# Sheet1.net
KiCad netlist of a schematic drawn in Altium Designer
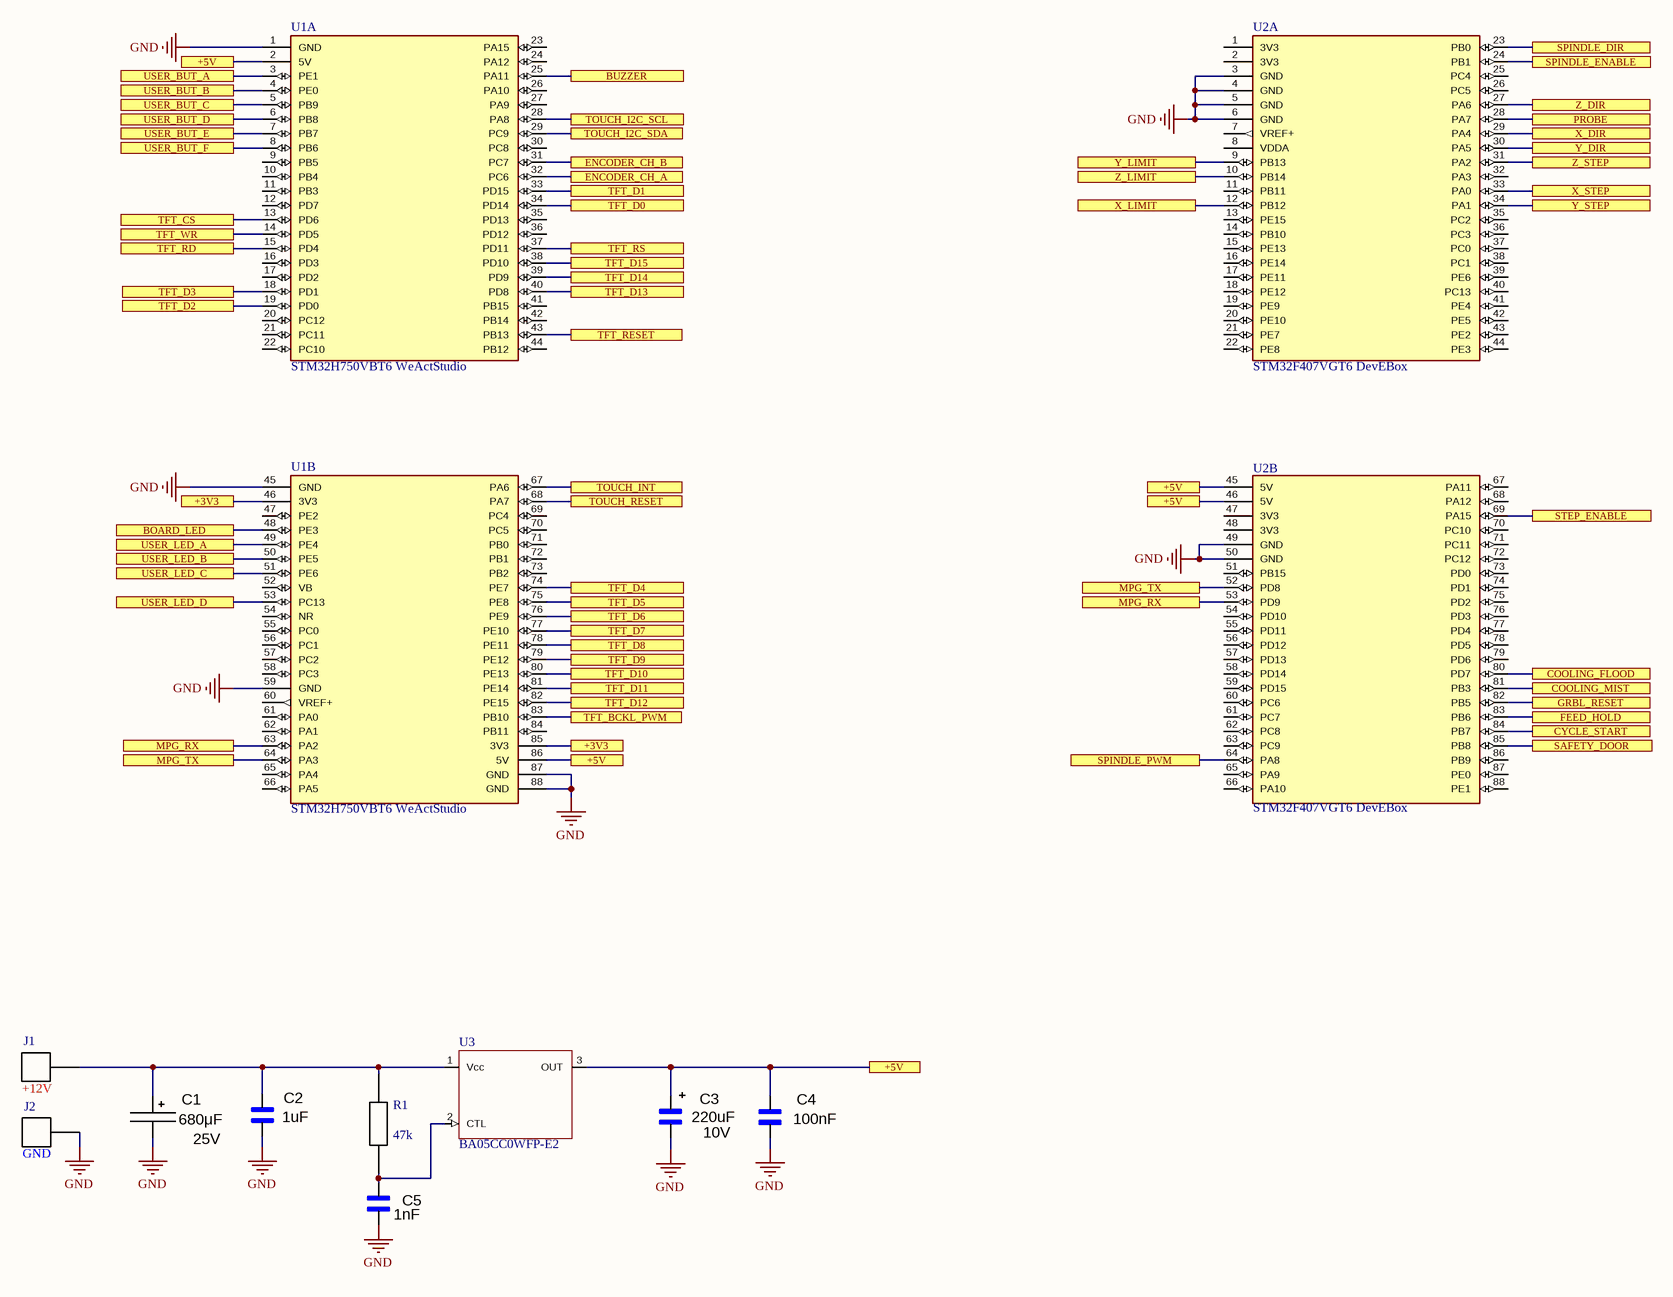
[diagram p0: Sheet1.SchDoc]

(export (version "E")
  (design (tool "Eeschema 10.0.6"))
  (components
    (comp (ref "C1")
      (value "680μF")
      (footprint "CAP 10x16")
      (fields
        (field (name "MANUFACTURER") "FUJICON")
        (field (name "VOLTAGE") "25V")
        (field (name "Comment") "680μF / 25V")
      )
      (libsource (lib "CAN_Library") (part "CAP Aluminium"))
    )
    (comp (ref "C2")
      (value "1uF")
      (footprint "*CAPC3326X230N")
      (description "C1210 10uF 35V X7R")
      (fields (field (name "MANUFACTURER") "SAMSUNG ELECTRO-MECHANICS"))
      (libsource (lib "CAN_Library") (part "CL32B106KLJNNNE"))
    )
    (comp (ref "C3")
      (value "220uF")
      (footprint "SMD 7343-43")
      (description "Cap Tant Solid 220uF 10V E CASE 10% _7.3 X 4.3 X 4mm_ SMD 7343-43 0.1 Ohm 125В°C T/R")
      (fields
        (field (name "MANUFACTURER") "VISHAY")
        (field (name "VOLTAGE") "10V")
        (field (name "Comment") "220uF 10V")
      )
      (libsource (lib "CAN_Library") (part "Cap Tant 220uF 10V Case E"))
    )
    (comp (ref "C4")
      (value "100nF")
      (footprint "SMD 0603")
      (description "C1210 10uF 35V X7R")
      (fields (field (name "MANUFACTURER") "SAMSUNG ELECTRO-MECHANICS"))
      (libsource (lib "CAN_Library") (part "CL32B106KLJNNNE"))
    )
    (comp (ref "C5")
      (value "1nF")
      (footprint "SMD 0603")
      (description "C1210 10uF 35V X7R")
      (fields (field (name "MANUFACTURER") "SAMSUNG ELECTRO-MECHANICS"))
      (libsource (lib "CAN_Library") (part "CL32B106KLJNNNE"))
    )
    (comp (ref "J1")
      (value "+12V")
      (footprint "Wire")
      (description "Wire")
      (libsource (lib "CAN_Library") (part "Wire"))
    )
    (comp (ref "J2")
      (value "GND")
      (footprint "Wire")
      (description "Wire")
      (libsource (lib "CAN_Library") (part "Wire"))
    )
    (comp (ref "R1")
      (value "47k")
      (footprint "SMD 0805")
      (description "RES")
      (libsource (lib "CAN_Library") (part "Resistor_1"))
    )
    (comp (ref "U1")
      (value "STM32H750VBT6 WeActStudio")
      (footprint "WeActStudio STM32H750VBT6")
      (libsource (lib "CAN_Library") (part "STM32H750VBT6 WeActStudio"))
    )
    (comp (ref "U2")
      (value "STM32F407VGT6 DevEBox")
      (footprint "DevEBox V3.0 STM32F407VGT6")
      (libsource (lib "CAN_Library") (part "STM32F407VGT6 DevEBox"))
    )
    (comp (ref "U3")
      (value "BA05CC0WFP-E2")
      (footprint "DPAK228P968X238-4N")
      (description "LDO Regulator")
      (fields (field (name "MANUFACTURER") "ROHM Semiconductor"))
      (libsource (lib "CAN_Library") (part "BA05CC0FP-E2"))
    )
  )
  (nets
    (net (code "1") (name "/+3V3") (class "Default")
      (node (ref "U1") (pin "46") (pinfunction "3V3_46") (pintype "power_in"))
      (node (ref "U1") (pin "85") (pinfunction "3V3_85") (pintype "power_in"))
    )
    (net (code "2") (name "/+5V") (class "Default")
      (node (ref "C3") (pin "1") (pinfunction "1_1") (pintype "passive"))
      (node (ref "C4") (pin "2") (pinfunction "2_2") (pintype "passive"))
      (node (ref "U1") (pin "2") (pinfunction "5V_2") (pintype "power_in"))
      (node (ref "U1") (pin "86") (pinfunction "5V_86") (pintype "power_in"))
      (node (ref "U2") (pin "45") (pinfunction "5V_45") (pintype "power_in"))
      (node (ref "U2") (pin "46") (pinfunction "5V_46") (pintype "power_in"))
      (node (ref "U3") (pin "3") (pinfunction "OUT_3") (pintype "passive"))
    )
    (net (code "3") (name "/BOARD_LED") (class "Default")
      (node (ref "U1") (pin "48") (pinfunction "PE3_48") (pintype "bidirectional"))
    )
    (net (code "4") (name "/BUZZER") (class "Default")
      (node (ref "U1") (pin "25") (pinfunction "PA11_25") (pintype "bidirectional"))
    )
    (net (code "5") (name "/COOLING_FLOOD") (class "Default")
      (node (ref "U2") (pin "80") (pinfunction "PD7_80") (pintype "bidirectional"))
    )
    (net (code "6") (name "/COOLING_MIST") (class "Default")
      (node (ref "U2") (pin "81") (pinfunction "PB3_81") (pintype "bidirectional"))
    )
    (net (code "7") (name "/CYCLE_START") (class "Default")
      (node (ref "U2") (pin "84") (pinfunction "PB7_84") (pintype "bidirectional"))
    )
    (net (code "8") (name "/ENCODER_CH_A") (class "Default")
      (node (ref "U1") (pin "32") (pinfunction "PC6_32") (pintype "bidirectional"))
    )
    (net (code "9") (name "/ENCODER_CH_B") (class "Default")
      (node (ref "U1") (pin "31") (pinfunction "PC7_31") (pintype "bidirectional"))
    )
    (net (code "10") (name "/FEED_HOLD") (class "Default")
      (node (ref "U2") (pin "83") (pinfunction "PB6_83") (pintype "bidirectional"))
    )
    (net (code "11") (name "/GRBL_RESET") (class "Default")
      (node (ref "U2") (pin "82") (pinfunction "PB5_82") (pintype "bidirectional"))
    )
    (net (code "12") (name "/MPG_RX") (class "Default")
      (node (ref "U1") (pin "63") (pinfunction "PA2_63") (pintype "bidirectional"))
      (node (ref "U2") (pin "53") (pinfunction "PD9_53") (pintype "bidirectional"))
    )
    (net (code "13") (name "/MPG_TX") (class "Default")
      (node (ref "U1") (pin "64") (pinfunction "PA3_64") (pintype "bidirectional"))
      (node (ref "U2") (pin "52") (pinfunction "PD8_52") (pintype "bidirectional"))
    )
    (net (code "14") (name "/PROBE") (class "Default")
      (node (ref "U2") (pin "28") (pinfunction "PA7_28") (pintype "bidirectional"))
    )
    (net (code "15") (name "/SAFETY_DOOR") (class "Default")
      (node (ref "U2") (pin "85") (pinfunction "PB8_85") (pintype "bidirectional"))
    )
    (net (code "16") (name "/SPINDLE_DIR") (class "Default")
      (node (ref "U2") (pin "23") (pinfunction "PB0_23") (pintype "bidirectional"))
    )
    (net (code "17") (name "/SPINDLE_ENABLE") (class "Default")
      (node (ref "U2") (pin "24") (pinfunction "PB1_24") (pintype "bidirectional"))
    )
    (net (code "18") (name "/SPINDLE_PWM") (class "Default")
      (node (ref "U2") (pin "64") (pinfunction "PA8_64") (pintype "bidirectional"))
    )
    (net (code "19") (name "/STEP_ENABLE") (class "Default")
      (node (ref "U2") (pin "69") (pinfunction "PA15_69") (pintype "bidirectional"))
    )
    (net (code "20") (name "/TFT_BCKL_PWM") (class "Default")
      (node (ref "U1") (pin "83") (pinfunction "PB10_83") (pintype "bidirectional"))
    )
    (net (code "21") (name "/TFT_CS") (class "Default")
      (node (ref "U1") (pin "13") (pinfunction "PD6_13") (pintype "bidirectional"))
    )
    (net (code "22") (name "/TFT_D0") (class "Default")
      (node (ref "U1") (pin "34") (pinfunction "PD14_34") (pintype "bidirectional"))
    )
    (net (code "23") (name "/TFT_D1") (class "Default")
      (node (ref "U1") (pin "33") (pinfunction "PD15_33") (pintype "bidirectional"))
    )
    (net (code "24") (name "/TFT_D2") (class "Default")
      (node (ref "U1") (pin "19") (pinfunction "PD0_19") (pintype "bidirectional"))
    )
    (net (code "25") (name "/TFT_D3") (class "Default")
      (node (ref "U1") (pin "18") (pinfunction "PD1_18") (pintype "bidirectional"))
    )
    (net (code "26") (name "/TFT_D4") (class "Default")
      (node (ref "U1") (pin "74") (pinfunction "PE7_74") (pintype "bidirectional"))
    )
    (net (code "27") (name "/TFT_D5") (class "Default")
      (node (ref "U1") (pin "75") (pinfunction "PE8_75") (pintype "bidirectional"))
    )
    (net (code "28") (name "/TFT_D6") (class "Default")
      (node (ref "U1") (pin "76") (pinfunction "PE9_76") (pintype "bidirectional"))
    )
    (net (code "29") (name "/TFT_D7") (class "Default")
      (node (ref "U1") (pin "77") (pinfunction "PE10_77") (pintype "bidirectional"))
    )
    (net (code "30") (name "/TFT_D8") (class "Default")
      (node (ref "U1") (pin "78") (pinfunction "PE11_78") (pintype "bidirectional"))
    )
    (net (code "31") (name "/TFT_D9") (class "Default")
      (node (ref "U1") (pin "79") (pinfunction "PE12_79") (pintype "bidirectional"))
    )
    (net (code "32") (name "/TFT_D10") (class "Default")
      (node (ref "U1") (pin "80") (pinfunction "PE13_80") (pintype "bidirectional"))
    )
    (net (code "33") (name "/TFT_D11") (class "Default")
      (node (ref "U1") (pin "81") (pinfunction "PE14_81") (pintype "bidirectional"))
    )
    (net (code "34") (name "/TFT_D12") (class "Default")
      (node (ref "U1") (pin "82") (pinfunction "PE15_82") (pintype "bidirectional"))
    )
    (net (code "35") (name "/TFT_D13") (class "Default")
      (node (ref "U1") (pin "40") (pinfunction "PD8_40") (pintype "bidirectional"))
    )
    (net (code "36") (name "/TFT_D14") (class "Default")
      (node (ref "U1") (pin "39") (pinfunction "PD9_39") (pintype "bidirectional"))
    )
    (net (code "37") (name "/TFT_D15") (class "Default")
      (node (ref "U1") (pin "38") (pinfunction "PD10_38") (pintype "bidirectional"))
    )
    (net (code "38") (name "/TFT_RD") (class "Default")
      (node (ref "U1") (pin "15") (pinfunction "PD4_15") (pintype "bidirectional"))
    )
    (net (code "39") (name "/TFT_RESET") (class "Default")
      (node (ref "U1") (pin "43") (pinfunction "PB13_43") (pintype "bidirectional"))
    )
    (net (code "40") (name "/TFT_RS") (class "Default")
      (node (ref "U1") (pin "37") (pinfunction "PD11_37") (pintype "bidirectional"))
    )
    (net (code "41") (name "/TFT_WR") (class "Default")
      (node (ref "U1") (pin "14") (pinfunction "PD5_14") (pintype "bidirectional"))
    )
    (net (code "42") (name "/TOUCH_I2C_SCL") (class "Default")
      (node (ref "U1") (pin "28") (pinfunction "PA8_28") (pintype "bidirectional"))
    )
    (net (code "43") (name "/TOUCH_I2C_SDA") (class "Default")
      (node (ref "U1") (pin "29") (pinfunction "PC9_29") (pintype "bidirectional"))
    )
    (net (code "44") (name "/TOUCH_INT") (class "Default")
      (node (ref "U1") (pin "67") (pinfunction "PA6_67") (pintype "bidirectional"))
    )
    (net (code "45") (name "/TOUCH_RESET") (class "Default")
      (node (ref "U1") (pin "68") (pinfunction "PA7_68") (pintype "bidirectional"))
    )
    (net (code "46") (name "/USER_BUT_A") (class "Default")
      (node (ref "U1") (pin "3") (pinfunction "PE1_3") (pintype "bidirectional"))
    )
    (net (code "47") (name "/USER_BUT_B") (class "Default")
      (node (ref "U1") (pin "4") (pinfunction "PE0_4") (pintype "bidirectional"))
    )
    (net (code "48") (name "/USER_BUT_C") (class "Default")
      (node (ref "U1") (pin "5") (pinfunction "PB9_5") (pintype "bidirectional"))
    )
    (net (code "49") (name "/USER_BUT_D") (class "Default")
      (node (ref "U1") (pin "6") (pinfunction "PB8_6") (pintype "bidirectional"))
    )
    (net (code "50") (name "/USER_BUT_E") (class "Default")
      (node (ref "U1") (pin "7") (pinfunction "PB7_7") (pintype "bidirectional"))
    )
    (net (code "51") (name "/USER_BUT_F") (class "Default")
      (node (ref "U1") (pin "8") (pinfunction "PB6_8") (pintype "bidirectional"))
    )
    (net (code "52") (name "/USER_LED_A") (class "Default")
      (node (ref "U1") (pin "49") (pinfunction "PE4_49") (pintype "bidirectional"))
    )
    (net (code "53") (name "/USER_LED_B") (class "Default")
      (node (ref "U1") (pin "50") (pinfunction "PE5_50") (pintype "bidirectional"))
    )
    (net (code "54") (name "/USER_LED_C") (class "Default")
      (node (ref "U1") (pin "51") (pinfunction "PE6_51") (pintype "bidirectional"))
    )
    (net (code "55") (name "/USER_LED_D") (class "Default")
      (node (ref "U1") (pin "53") (pinfunction "PC13_53") (pintype "bidirectional"))
    )
    (net (code "56") (name "/X_DIR") (class "Default")
      (node (ref "U2") (pin "29") (pinfunction "PA4_29") (pintype "bidirectional"))
    )
    (net (code "57") (name "/X_LIMIT") (class "Default")
      (node (ref "U2") (pin "12") (pinfunction "PB12_12") (pintype "bidirectional"))
    )
    (net (code "58") (name "/X_STEP") (class "Default")
      (node (ref "U2") (pin "33") (pinfunction "PA0_33") (pintype "bidirectional"))
    )
    (net (code "59") (name "/Y_DIR") (class "Default")
      (node (ref "U2") (pin "30") (pinfunction "PA5_30") (pintype "bidirectional"))
    )
    (net (code "60") (name "/Y_LIMIT") (class "Default")
      (node (ref "U2") (pin "9") (pinfunction "PB13_9") (pintype "bidirectional"))
    )
    (net (code "61") (name "/Y_STEP") (class "Default")
      (node (ref "U2") (pin "34") (pinfunction "PA1_34") (pintype "bidirectional"))
    )
    (net (code "62") (name "/Z_DIR") (class "Default")
      (node (ref "U2") (pin "27") (pinfunction "PA6_27") (pintype "bidirectional"))
    )
    (net (code "63") (name "/Z_LIMIT") (class "Default")
      (node (ref "U2") (pin "10") (pinfunction "PB14_10") (pintype "bidirectional"))
    )
    (net (code "64") (name "/Z_STEP") (class "Default")
      (node (ref "U2") (pin "31") (pinfunction "PA2_31") (pintype "bidirectional"))
    )
    (net (code "65") (name "GND") (class "Default")
      (node (ref "C1") (pin "2") (pinfunction "2_2") (pintype "power_in"))
      (node (ref "C2") (pin "1") (pinfunction "1_1") (pintype "passive"))
      (node (ref "C3") (pin "2") (pinfunction "2_2") (pintype "passive"))
      (node (ref "C4") (pin "1") (pinfunction "1_1") (pintype "passive"))
      (node (ref "C5") (pin "1") (pinfunction "1_1") (pintype "passive"))
      (node (ref "J2") (pin "1") (pinfunction "1_1") (pintype "passive"))
      (node (ref "U1") (pin "1") (pinfunction "GND_1") (pintype "power_in"))
      (node (ref "U1") (pin "45") (pinfunction "GND_45") (pintype "power_in"))
      (node (ref "U1") (pin "59") (pinfunction "GND_59") (pintype "power_in"))
      (node (ref "U1") (pin "87") (pinfunction "GND_87") (pintype "power_in"))
      (node (ref "U1") (pin "88") (pinfunction "GND_88") (pintype "power_in"))
      (node (ref "U2") (pin "3") (pinfunction "GND_3") (pintype "power_in"))
      (node (ref "U2") (pin "4") (pinfunction "GND_4") (pintype "power_in"))
      (node (ref "U2") (pin "49") (pinfunction "GND_49") (pintype "power_in"))
      (node (ref "U2") (pin "5") (pinfunction "GND_5") (pintype "power_in"))
      (node (ref "U2") (pin "50") (pinfunction "GND_50") (pintype "power_in"))
      (node (ref "U2") (pin "6") (pinfunction "GND_6") (pintype "power_in"))
    )
    (net (code "66") (name "Net-(U3-CTL)") (class "Default")
      (node (ref "C5") (pin "2") (pinfunction "2_2") (pintype "passive"))
      (node (ref "R1") (pin "2") (pinfunction "2_2") (pintype "passive"))
      (node (ref "U3") (pin "2") (pinfunction "CTL_2") (pintype "input"))
    )
    (net (code "67") (name "Net-(U3-Vcc)") (class "Default")
      (node (ref "C1") (pin "1") (pinfunction "1_1") (pintype "power_in"))
      (node (ref "C2") (pin "2") (pinfunction "2_2") (pintype "passive"))
      (node (ref "J1") (pin "1") (pinfunction "1_1") (pintype "passive"))
      (node (ref "R1") (pin "1") (pinfunction "1_1") (pintype "passive"))
      (node (ref "U3") (pin "1") (pinfunction "Vcc_1") (pintype "power_in"))
    )
    (net (code "68") (name "unconnected-(U1A-PA9-Pad27)") (class "Default")
      (node (ref "U1") (pin "27") (pinfunction "PA9_27") (pintype "bidirectional"))
    )
    (net (code "69") (name "unconnected-(U1A-PA10-Pad26)") (class "Default")
      (node (ref "U1") (pin "26") (pinfunction "PA10_26") (pintype "bidirectional"))
    )
    (net (code "70") (name "unconnected-(U1A-PA12-Pad24)") (class "Default")
      (node (ref "U1") (pin "24") (pinfunction "PA12_24") (pintype "bidirectional"))
    )
    (net (code "71") (name "unconnected-(U1A-PA15-Pad23)") (class "Default")
      (node (ref "U1") (pin "23") (pinfunction "PA15_23") (pintype "bidirectional"))
    )
    (net (code "72") (name "unconnected-(U1A-PB3-Pad11)") (class "Default")
      (node (ref "U1") (pin "11") (pinfunction "PB3_11") (pintype "bidirectional"))
    )
    (net (code "73") (name "unconnected-(U1A-PB4-Pad10)") (class "Default")
      (node (ref "U1") (pin "10") (pinfunction "PB4_10") (pintype "bidirectional"))
    )
    (net (code "74") (name "unconnected-(U1A-PB5-Pad9)") (class "Default")
      (node (ref "U1") (pin "9") (pinfunction "PB5_9") (pintype "bidirectional"))
    )
    (net (code "75") (name "unconnected-(U1A-PB12-Pad44)") (class "Default")
      (node (ref "U1") (pin "44") (pinfunction "PB12_44") (pintype "bidirectional"))
    )
    (net (code "76") (name "unconnected-(U1A-PB14-Pad42)") (class "Default")
      (node (ref "U1") (pin "42") (pinfunction "PB14_42") (pintype "bidirectional"))
    )
    (net (code "77") (name "unconnected-(U1A-PB15-Pad41)") (class "Default")
      (node (ref "U1") (pin "41") (pinfunction "PB15_41") (pintype "bidirectional"))
    )
    (net (code "78") (name "unconnected-(U1A-PC8-Pad30)") (class "Default")
      (node (ref "U1") (pin "30") (pinfunction "PC8_30") (pintype "bidirectional"))
    )
    (net (code "79") (name "unconnected-(U1A-PC10-Pad22)") (class "Default")
      (node (ref "U1") (pin "22") (pinfunction "PC10_22") (pintype "bidirectional"))
    )
    (net (code "80") (name "unconnected-(U1A-PC11-Pad21)") (class "Default")
      (node (ref "U1") (pin "21") (pinfunction "PC11_21") (pintype "bidirectional"))
    )
    (net (code "81") (name "unconnected-(U1A-PC12-Pad20)") (class "Default")
      (node (ref "U1") (pin "20") (pinfunction "PC12_20") (pintype "bidirectional"))
    )
    (net (code "82") (name "unconnected-(U1A-PD2-Pad17)") (class "Default")
      (node (ref "U1") (pin "17") (pinfunction "PD2_17") (pintype "bidirectional"))
    )
    (net (code "83") (name "unconnected-(U1A-PD3-Pad16)") (class "Default")
      (node (ref "U1") (pin "16") (pinfunction "PD3_16") (pintype "bidirectional"))
    )
    (net (code "84") (name "unconnected-(U1A-PD7-Pad12)") (class "Default")
      (node (ref "U1") (pin "12") (pinfunction "PD7_12") (pintype "bidirectional"))
    )
    (net (code "85") (name "unconnected-(U1A-PD12-Pad36)") (class "Default")
      (node (ref "U1") (pin "36") (pinfunction "PD12_36") (pintype "bidirectional"))
    )
    (net (code "86") (name "unconnected-(U1A-PD13-Pad35)") (class "Default")
      (node (ref "U1") (pin "35") (pinfunction "PD13_35") (pintype "bidirectional"))
    )
    (net (code "87") (name "unconnected-(U1B-NR-Pad54)") (class "Default")
      (node (ref "U1") (pin "54") (pinfunction "NR_54") (pintype "bidirectional"))
    )
    (net (code "88") (name "unconnected-(U1B-PA0-Pad61)") (class "Default")
      (node (ref "U1") (pin "61") (pinfunction "PA0_61") (pintype "bidirectional"))
    )
    (net (code "89") (name "unconnected-(U1B-PA1-Pad62)") (class "Default")
      (node (ref "U1") (pin "62") (pinfunction "PA1_62") (pintype "bidirectional"))
    )
    (net (code "90") (name "unconnected-(U1B-PA4-Pad65)") (class "Default")
      (node (ref "U1") (pin "65") (pinfunction "PA4_65") (pintype "bidirectional"))
    )
    (net (code "91") (name "unconnected-(U1B-PA5-Pad66)") (class "Default")
      (node (ref "U1") (pin "66") (pinfunction "PA5_66") (pintype "bidirectional"))
    )
    (net (code "92") (name "unconnected-(U1B-PB0-Pad71)") (class "Default")
      (node (ref "U1") (pin "71") (pinfunction "PB0_71") (pintype "bidirectional"))
    )
    (net (code "93") (name "unconnected-(U1B-PB1-Pad72)") (class "Default")
      (node (ref "U1") (pin "72") (pinfunction "PB1_72") (pintype "bidirectional"))
    )
    (net (code "94") (name "unconnected-(U1B-PB2-Pad73)") (class "Default")
      (node (ref "U1") (pin "73") (pinfunction "PB2_73") (pintype "bidirectional"))
    )
    (net (code "95") (name "unconnected-(U1B-PB11-Pad84)") (class "Default")
      (node (ref "U1") (pin "84") (pinfunction "PB11_84") (pintype "bidirectional"))
    )
    (net (code "96") (name "unconnected-(U1B-PC0-Pad55)") (class "Default")
      (node (ref "U1") (pin "55") (pinfunction "PC0_55") (pintype "bidirectional"))
    )
    (net (code "97") (name "unconnected-(U1B-PC1-Pad56)") (class "Default")
      (node (ref "U1") (pin "56") (pinfunction "PC1_56") (pintype "bidirectional"))
    )
    (net (code "98") (name "unconnected-(U1B-PC2-Pad57)") (class "Default")
      (node (ref "U1") (pin "57") (pinfunction "PC2_57") (pintype "bidirectional"))
    )
    (net (code "99") (name "unconnected-(U1B-PC3-Pad58)") (class "Default")
      (node (ref "U1") (pin "58") (pinfunction "PC3_58") (pintype "bidirectional"))
    )
    (net (code "100") (name "unconnected-(U1B-PC4-Pad69)") (class "Default")
      (node (ref "U1") (pin "69") (pinfunction "PC4_69") (pintype "bidirectional"))
    )
    (net (code "101") (name "unconnected-(U1B-PC5-Pad70)") (class "Default")
      (node (ref "U1") (pin "70") (pinfunction "PC5_70") (pintype "bidirectional"))
    )
    (net (code "102") (name "unconnected-(U1B-PE2-Pad47)") (class "Default")
      (node (ref "U1") (pin "47") (pinfunction "PE2_47") (pintype "bidirectional"))
    )
    (net (code "103") (name "unconnected-(U1B-VB-Pad52)") (class "Default")
      (node (ref "U1") (pin "52") (pinfunction "VB_52") (pintype "bidirectional"))
    )
    (net (code "104") (name "unconnected-(U1B-VREF+-Pad60)") (class "Default")
      (node (ref "U1") (pin "60") (pinfunction "VREF+_60") (pintype "output"))
    )
    (net (code "105") (name "unconnected-(U2A-3V3-Pad1)") (class "Default")
      (node (ref "U2") (pin "1") (pinfunction "3V3_1") (pintype "power_in"))
    )
    (net (code "106") (name "unconnected-(U2A-3V3-Pad2)") (class "Default")
      (node (ref "U2") (pin "2") (pinfunction "3V3_2") (pintype "power_in"))
    )
    (net (code "107") (name "unconnected-(U2A-PA3-Pad32)") (class "Default")
      (node (ref "U2") (pin "32") (pinfunction "PA3_32") (pintype "bidirectional"))
    )
    (net (code "108") (name "unconnected-(U2A-PB10-Pad14)") (class "Default")
      (node (ref "U2") (pin "14") (pinfunction "PB10_14") (pintype "bidirectional"))
    )
    (net (code "109") (name "unconnected-(U2A-PB11-Pad11)") (class "Default")
      (node (ref "U2") (pin "11") (pinfunction "PB11_11") (pintype "bidirectional"))
    )
    (net (code "110") (name "unconnected-(U2A-PC0-Pad37)") (class "Default")
      (node (ref "U2") (pin "37") (pinfunction "PC0_37") (pintype "bidirectional"))
    )
    (net (code "111") (name "unconnected-(U2A-PC1-Pad38)") (class "Default")
      (node (ref "U2") (pin "38") (pinfunction "PC1_38") (pintype "bidirectional"))
    )
    (net (code "112") (name "unconnected-(U2A-PC2-Pad35)") (class "Default")
      (node (ref "U2") (pin "35") (pinfunction "PC2_35") (pintype "bidirectional"))
    )
    (net (code "113") (name "unconnected-(U2A-PC3-Pad36)") (class "Default")
      (node (ref "U2") (pin "36") (pinfunction "PC3_36") (pintype "bidirectional"))
    )
    (net (code "114") (name "unconnected-(U2A-PC4-Pad25)") (class "Default")
      (node (ref "U2") (pin "25") (pinfunction "PC4_25") (pintype "bidirectional"))
    )
    (net (code "115") (name "unconnected-(U2A-PC5-Pad26)") (class "Default")
      (node (ref "U2") (pin "26") (pinfunction "PC5_26") (pintype "bidirectional"))
    )
    (net (code "116") (name "unconnected-(U2A-PC13-Pad40)") (class "Default")
      (node (ref "U2") (pin "40") (pinfunction "PC13_40") (pintype "bidirectional"))
    )
    (net (code "117") (name "unconnected-(U2A-PE2-Pad43)") (class "Default")
      (node (ref "U2") (pin "43") (pinfunction "PE2_43") (pintype "bidirectional"))
    )
    (net (code "118") (name "unconnected-(U2A-PE3-Pad44)") (class "Default")
      (node (ref "U2") (pin "44") (pinfunction "PE3_44") (pintype "bidirectional"))
    )
    (net (code "119") (name "unconnected-(U2A-PE4-Pad41)") (class "Default")
      (node (ref "U2") (pin "41") (pinfunction "PE4_41") (pintype "bidirectional"))
    )
    (net (code "120") (name "unconnected-(U2A-PE5-Pad42)") (class "Default")
      (node (ref "U2") (pin "42") (pinfunction "PE5_42") (pintype "bidirectional"))
    )
    (net (code "121") (name "unconnected-(U2A-PE6-Pad39)") (class "Default")
      (node (ref "U2") (pin "39") (pinfunction "PE6_39") (pintype "bidirectional"))
    )
    (net (code "122") (name "unconnected-(U2A-PE7-Pad21)") (class "Default")
      (node (ref "U2") (pin "21") (pinfunction "PE7_21") (pintype "bidirectional"))
    )
    (net (code "123") (name "unconnected-(U2A-PE8-Pad22)") (class "Default")
      (node (ref "U2") (pin "22") (pinfunction "PE8_22") (pintype "bidirectional"))
    )
    (net (code "124") (name "unconnected-(U2A-PE9-Pad19)") (class "Default")
      (node (ref "U2") (pin "19") (pinfunction "PE9_19") (pintype "bidirectional"))
    )
    (net (code "125") (name "unconnected-(U2A-PE10-Pad20)") (class "Default")
      (node (ref "U2") (pin "20") (pinfunction "PE10_20") (pintype "bidirectional"))
    )
    (net (code "126") (name "unconnected-(U2A-PE11-Pad17)") (class "Default")
      (node (ref "U2") (pin "17") (pinfunction "PE11_17") (pintype "bidirectional"))
    )
    (net (code "127") (name "unconnected-(U2A-PE12-Pad18)") (class "Default")
      (node (ref "U2") (pin "18") (pinfunction "PE12_18") (pintype "bidirectional"))
    )
    (net (code "128") (name "unconnected-(U2A-PE13-Pad15)") (class "Default")
      (node (ref "U2") (pin "15") (pinfunction "PE13_15") (pintype "bidirectional"))
    )
    (net (code "129") (name "unconnected-(U2A-PE14-Pad16)") (class "Default")
      (node (ref "U2") (pin "16") (pinfunction "PE14_16") (pintype "bidirectional"))
    )
    (net (code "130") (name "unconnected-(U2A-PE15-Pad13)") (class "Default")
      (node (ref "U2") (pin "13") (pinfunction "PE15_13") (pintype "bidirectional"))
    )
    (net (code "131") (name "unconnected-(U2A-VDDA-Pad8)") (class "Default")
      (node (ref "U2") (pin "8") (pinfunction "VDDA_8") (pintype "power_in"))
    )
    (net (code "132") (name "unconnected-(U2A-VREF+-Pad7)") (class "Default")
      (node (ref "U2") (pin "7") (pinfunction "VREF+_7") (pintype "output"))
    )
    (net (code "133") (name "unconnected-(U2B-3V3-Pad47)") (class "Default")
      (node (ref "U2") (pin "47") (pinfunction "3V3_47") (pintype "power_in"))
    )
    (net (code "134") (name "unconnected-(U2B-3V3-Pad48)") (class "Default")
      (node (ref "U2") (pin "48") (pinfunction "3V3_48") (pintype "power_in"))
    )
    (net (code "135") (name "unconnected-(U2B-PA9-Pad65)") (class "Default")
      (node (ref "U2") (pin "65") (pinfunction "PA9_65") (pintype "bidirectional"))
    )
    (net (code "136") (name "unconnected-(U2B-PA10-Pad66)") (class "Default")
      (node (ref "U2") (pin "66") (pinfunction "PA10_66") (pintype "bidirectional"))
    )
    (net (code "137") (name "unconnected-(U2B-PA11-Pad67)") (class "Default")
      (node (ref "U2") (pin "67") (pinfunction "PA11_67") (pintype "bidirectional"))
    )
    (net (code "138") (name "unconnected-(U2B-PA12-Pad68)") (class "Default")
      (node (ref "U2") (pin "68") (pinfunction "PA12_68") (pintype "bidirectional"))
    )
    (net (code "139") (name "unconnected-(U2B-PB9-Pad86)") (class "Default")
      (node (ref "U2") (pin "86") (pinfunction "PB9_86") (pintype "bidirectional"))
    )
    (net (code "140") (name "unconnected-(U2B-PB15-Pad51)") (class "Default")
      (node (ref "U2") (pin "51") (pinfunction "PB15_51") (pintype "bidirectional"))
    )
    (net (code "141") (name "unconnected-(U2B-PC6-Pad60)") (class "Default")
      (node (ref "U2") (pin "60") (pinfunction "PC6_60") (pintype "bidirectional"))
    )
    (net (code "142") (name "unconnected-(U2B-PC7-Pad61)") (class "Default")
      (node (ref "U2") (pin "61") (pinfunction "PC7_61") (pintype "bidirectional"))
    )
    (net (code "143") (name "unconnected-(U2B-PC8-Pad62)") (class "Default")
      (node (ref "U2") (pin "62") (pinfunction "PC8_62") (pintype "bidirectional"))
    )
    (net (code "144") (name "unconnected-(U2B-PC9-Pad63)") (class "Default")
      (node (ref "U2") (pin "63") (pinfunction "PC9_63") (pintype "bidirectional"))
    )
    (net (code "145") (name "unconnected-(U2B-PC10-Pad70)") (class "Default")
      (node (ref "U2") (pin "70") (pinfunction "PC10_70") (pintype "bidirectional"))
    )
    (net (code "146") (name "unconnected-(U2B-PC11-Pad71)") (class "Default")
      (node (ref "U2") (pin "71") (pinfunction "PC11_71") (pintype "bidirectional"))
    )
    (net (code "147") (name "unconnected-(U2B-PC12-Pad72)") (class "Default")
      (node (ref "U2") (pin "72") (pinfunction "PC12_72") (pintype "bidirectional"))
    )
    (net (code "148") (name "unconnected-(U2B-PD0-Pad73)") (class "Default")
      (node (ref "U2") (pin "73") (pinfunction "PD0_73") (pintype "bidirectional"))
    )
    (net (code "149") (name "unconnected-(U2B-PD1-Pad74)") (class "Default")
      (node (ref "U2") (pin "74") (pinfunction "PD1_74") (pintype "bidirectional"))
    )
    (net (code "150") (name "unconnected-(U2B-PD2-Pad75)") (class "Default")
      (node (ref "U2") (pin "75") (pinfunction "PD2_75") (pintype "bidirectional"))
    )
    (net (code "151") (name "unconnected-(U2B-PD3-Pad76)") (class "Default")
      (node (ref "U2") (pin "76") (pinfunction "PD3_76") (pintype "bidirectional"))
    )
    (net (code "152") (name "unconnected-(U2B-PD4-Pad77)") (class "Default")
      (node (ref "U2") (pin "77") (pinfunction "PD4_77") (pintype "bidirectional"))
    )
    (net (code "153") (name "unconnected-(U2B-PD5-Pad78)") (class "Default")
      (node (ref "U2") (pin "78") (pinfunction "PD5_78") (pintype "bidirectional"))
    )
    (net (code "154") (name "unconnected-(U2B-PD6-Pad79)") (class "Default")
      (node (ref "U2") (pin "79") (pinfunction "PD6_79") (pintype "bidirectional"))
    )
    (net (code "155") (name "unconnected-(U2B-PD10-Pad54)") (class "Default")
      (node (ref "U2") (pin "54") (pinfunction "PD10_54") (pintype "bidirectional"))
    )
    (net (code "156") (name "unconnected-(U2B-PD11-Pad55)") (class "Default")
      (node (ref "U2") (pin "55") (pinfunction "PD11_55") (pintype "bidirectional"))
    )
    (net (code "157") (name "unconnected-(U2B-PD12-Pad56)") (class "Default")
      (node (ref "U2") (pin "56") (pinfunction "PD12_56") (pintype "bidirectional"))
    )
    (net (code "158") (name "unconnected-(U2B-PD13-Pad57)") (class "Default")
      (node (ref "U2") (pin "57") (pinfunction "PD13_57") (pintype "bidirectional"))
    )
    (net (code "159") (name "unconnected-(U2B-PD14-Pad58)") (class "Default")
      (node (ref "U2") (pin "58") (pinfunction "PD14_58") (pintype "bidirectional"))
    )
    (net (code "160") (name "unconnected-(U2B-PD15-Pad59)") (class "Default")
      (node (ref "U2") (pin "59") (pinfunction "PD15_59") (pintype "bidirectional"))
    )
    (net (code "161") (name "unconnected-(U2B-PE0-Pad87)") (class "Default")
      (node (ref "U2") (pin "87") (pinfunction "PE0_87") (pintype "bidirectional"))
    )
    (net (code "162") (name "unconnected-(U2B-PE1-Pad88)") (class "Default")
      (node (ref "U2") (pin "88") (pinfunction "PE1_88") (pintype "bidirectional"))
    )
  )
)
